# Pre_Charge_Interface.net
KiCad netlist of a schematic drawn in Altium Designer
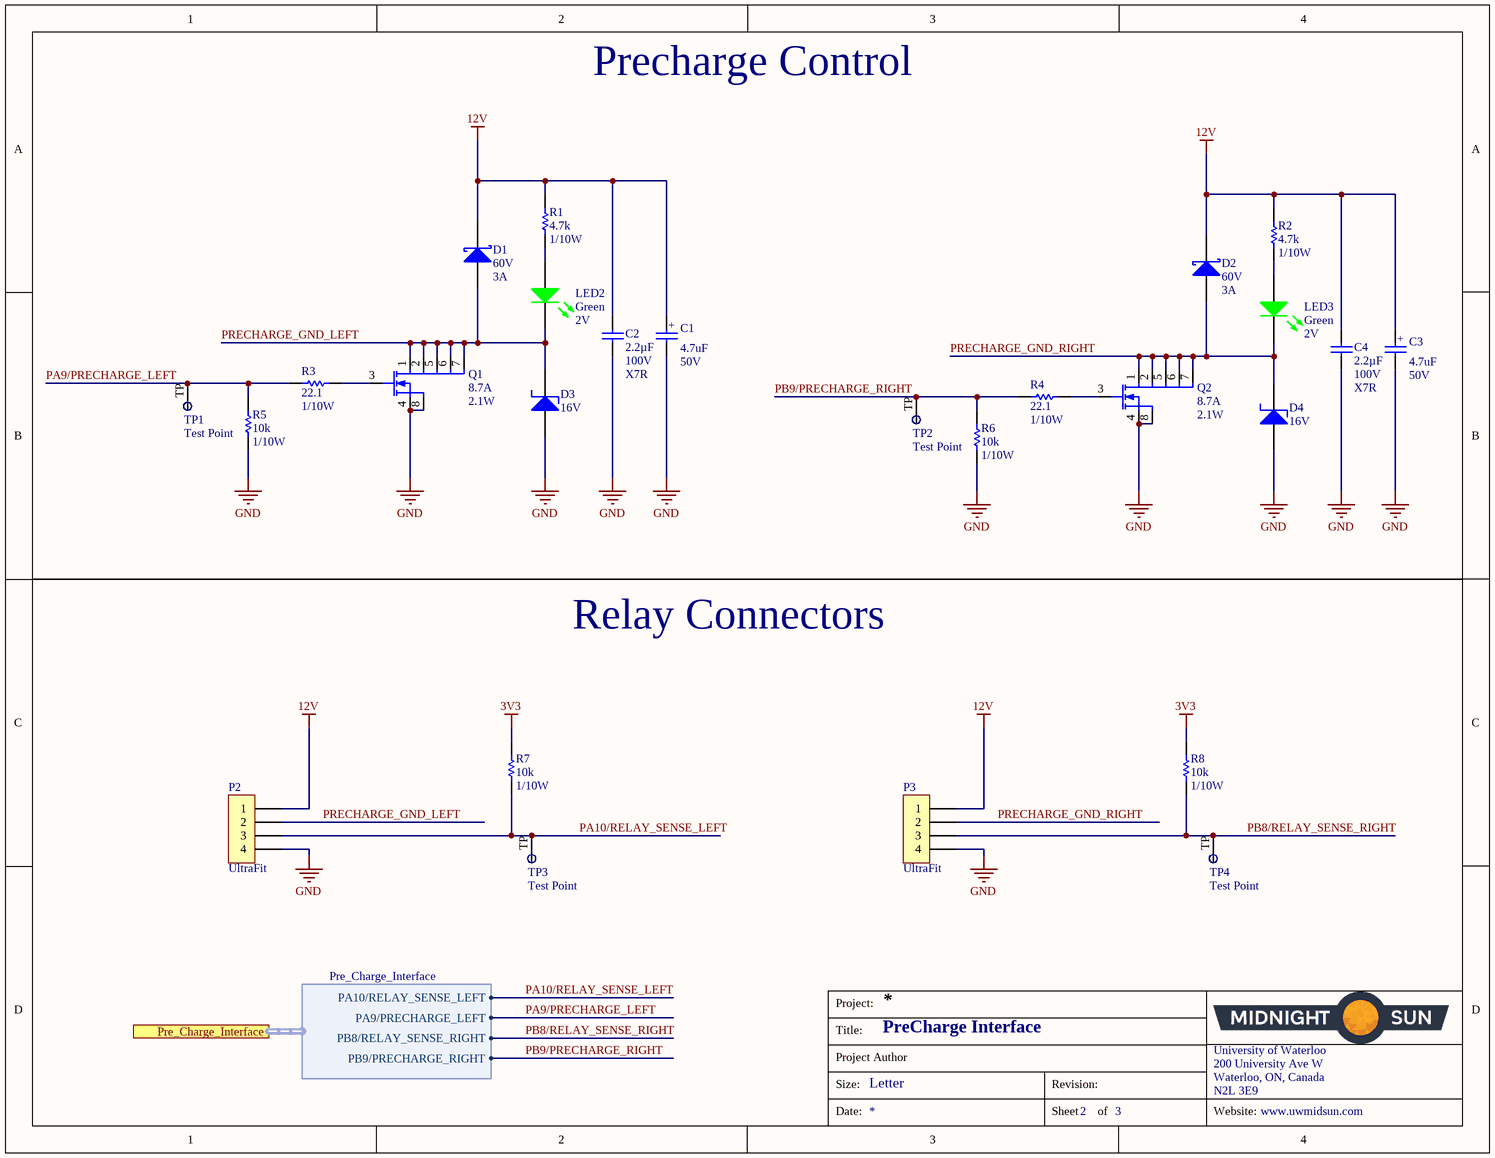
[diagram p0: Pre_Charge_Interface.SchDoc]

(export (version "E")
  (design (tool "Eeschema 10.0.6"))
  (components
    (comp (ref "C1")
      (value "EEE-1HA4R7NP")
      (footprint "CAP ALUM 6.3MM RADIAL SMD")
      (description "4.7µF 50V Aluminum Electrolytic Capacitors Radial, Can - SMD 2000 Hrs @ 85°C")
      (fields
        (field (name "TOLERANCE") "20%")
        (field (name "CAPACITANCE") "4.7uF")
        (field (name "VOLTAGE RATING (DC)") "50V")
      )
      (libsource (lib "Schematic Diagrams") (part "CAP ALUM 4.7UF 20% 50V SMD"))
    )
    (comp (ref "C2")
      (value "CAP CER 2.2UF 100V ±20% X7R 1206")
      (footprint "CAP, 1206")
      (description "2.2µF ±20% 100V Ceramic Capacitor X7R 1206 (3216 Metric)")
      (fields
        (field (name "TOLERANCE") "±20%")
        (field (name "CAPACITANCE") "2.2µF")
        (field (name "VOLTAGE") "100V")
        (field (name "TEMPERATURE COEFFICIENT") "X7R")
      )
      (libsource (lib "Schematic Diagrams") (part "CAP CER 2.2UF 100V ±20% X7R 1206"))
    )
    (comp (ref "C3")
      (value "EEE-1HA4R7NP")
      (footprint "CAP ALUM 6.3MM RADIAL SMD")
      (description "4.7µF 50V Aluminum Electrolytic Capacitors Radial, Can - SMD 2000 Hrs @ 85°C")
      (fields
        (field (name "TOLERANCE") "20%")
        (field (name "CAPACITANCE") "4.7uF")
        (field (name "VOLTAGE RATING (DC)") "50V")
      )
      (libsource (lib "Schematic Diagrams") (part "CAP ALUM 4.7UF 20% 50V SMD"))
    )
    (comp (ref "C4")
      (value "CAP CER 2.2UF 100V ±20% X7R 1206")
      (footprint "CAP, 1206")
      (description "2.2µF ±20% 100V Ceramic Capacitor X7R 1206 (3216 Metric)")
      (fields
        (field (name "TOLERANCE") "±20%")
        (field (name "CAPACITANCE") "2.2µF")
        (field (name "VOLTAGE") "100V")
        (field (name "TEMPERATURE COEFFICIENT") "X7R")
      )
      (libsource (lib "Schematic Diagrams") (part "CAP CER 2.2UF 100V ±20% X7R 1206"))
    )
    (comp (ref "D1")
      (value "DIODE SCHOTTKY 60V 3A SMA")
      (footprint "Diode, SMA")
      (description "Diode Schottky 60V 3A Surface Mount SMA")
      (fields
        (field (name "VOLTAGE - DC REVERSE (VR) (MAX)") "60V")
        (field (name "CURRENT - AVERAGE RECTIFIED (IO)") "3A")
      )
      (libsource (lib "Schematic Diagrams") (part "DIODE SCHOTTKY 60V 3A SMA"))
    )
    (comp (ref "D2")
      (value "DIODE SCHOTTKY 60V 3A SMA")
      (footprint "Diode, SMA")
      (description "Diode Schottky 60V 3A Surface Mount SMA")
      (fields
        (field (name "VOLTAGE - DC REVERSE (VR) (MAX)") "60V")
        (field (name "CURRENT - AVERAGE RECTIFIED (IO)") "3A")
      )
      (libsource (lib "Schematic Diagrams") (part "DIODE SCHOTTKY 60V 3A SMA"))
    )
    (comp (ref "D3")
      (value "DIODE ZENER 16V 5W DO-214AA (SMB)")
      (footprint "DO-214AA Diode")
      (description "Zener Diode 16V 5W ±5% Surface Mount DO-214AA (SMB)")
      (fields
        (field (name "MANUFACTURE PART NUMBER") "SMBJ5353B-TP")
        (field (name "VOLTAGE - ZENER (NOM)") "16V")
      )
      (libsource (lib "Schematic Diagrams") (part "DIODE ZENER 16V 5W DO-214AA (SMB)"))
    )
    (comp (ref "D4")
      (value "DIODE ZENER 16V 5W DO-214AA (SMB)")
      (footprint "DO-214AA Diode")
      (description "Zener Diode 16V 5W ±5% Surface Mount DO-214AA (SMB)")
      (fields
        (field (name "MANUFACTURE PART NUMBER") "SMBJ5353B-TP")
        (field (name "VOLTAGE - ZENER (NOM)") "16V")
      )
      (libsource (lib "Schematic Diagrams") (part "DIODE ZENER 16V 5W DO-214AA (SMB)"))
    )
    (comp (ref "LED2")
      (value "LED GREEN CLEAR 2V 0603")
      (footprint "LED_0603")
      (description "Green 572nm LED Indication - Discrete 2V 0603 (1608 Metric)")
      (fields
        (field (name "MANUFACTURER") "Wurth Electronics Inc.")
        (field (name "MANUFACTURER PART NUMBER") "150060VS75000")
        (field (name "COLOR") "Green")
        (field (name "VOLTAGE - FORWARD (VF) (TYP)") "2V")
      )
      (libsource (lib "Schematic Diagrams") (part "LED GREEN CLEAR 2V 0603"))
    )
    (comp (ref "LED3")
      (value "LED GREEN CLEAR 2V 0603")
      (footprint "LED_0603")
      (description "Green 572nm LED Indication - Discrete 2V 0603 (1608 Metric)")
      (fields
        (field (name "MANUFACTURER") "Wurth Electronics Inc.")
        (field (name "MANUFACTURER PART NUMBER") "150060VS75000")
        (field (name "COLOR") "Green")
        (field (name "VOLTAGE - FORWARD (VF) (TYP)") "2V")
      )
      (libsource (lib "Schematic Diagrams") (part "LED GREEN CLEAR 2V 0603"))
    )
    (comp (ref "P2")
      (value "CONN 4POS ULTRA-FIT 0.138\"")
      (footprint "CONN, 4POS ULTRA-FIT")
      (description "4 Positions Header Connector 0.138\" (3.50mm) Through Hole Tin")
      (fields (field (name "VOLTAGE") "400V") (field (name "SERIES") "UltraFit"))
      (libsource (lib "Schematic Diagrams") (part "CONN 4POS ULTRA-FIT 0.138{dblquote}"))
    )
    (comp (ref "P3")
      (value "CONN 4POS ULTRA-FIT 0.138\"")
      (footprint "CONN, 4POS ULTRA-FIT")
      (description "4 Positions Header Connector 0.138\" (3.50mm) Through Hole Tin")
      (fields (field (name "VOLTAGE") "400V") (field (name "SERIES") "UltraFit"))
      (libsource (lib "Schematic Diagrams") (part "CONN 4POS ULTRA-FIT 0.138{dblquote}"))
    )
    (comp (ref "Q1")
      (value "MOSFET N-CH 30V 8.7A 2.1W 6-PQFN (2x2)")
      (footprint "MOSFET N-CH 30V 12A 2mmx2mm PQFN")
      (fields
        (field (name "CURRENT - CONTINUOUS DRAIN (ID) @ 25°C") "8.7A")
        (field (name "POWER DISSIPATION (MAX)") "2.1W")
      )
      (libsource (lib "Schematic Diagrams") (part "MOSFET N-CH 30V 8.7A 2.1W 6-PQFN (2x2)"))
    )
    (comp (ref "Q2")
      (value "MOSFET N-CH 30V 8.7A 2.1W 6-PQFN (2x2)")
      (footprint "MOSFET N-CH 30V 12A 2mmx2mm PQFN")
      (fields
        (field (name "CURRENT - CONTINUOUS DRAIN (ID) @ 25°C") "8.7A")
        (field (name "POWER DISSIPATION (MAX)") "2.1W")
      )
      (libsource (lib "Schematic Diagrams") (part "MOSFET N-CH 30V 8.7A 2.1W 6-PQFN (2x2)"))
    )
    (comp (ref "R1")
      (value "RES 4.7K OHM 1% 1/10W 0603")
      (footprint "RES, 0603")
      (description "4.7k Ohm ±1% 0.1W, 1/10W Chip Resistor 0603 (1608 Metric) Moisture Resistant Thick Film")
      (fields
        (field (name "TOLERANCE") "±1%")
        (field (name "RESISTANCE (OHMS)") "4.7k")
        (field (name "POWER (WATTS)") "1/10W")
      )
      (libsource (lib "Schematic Diagrams") (part "RES 4.7K OHM 1% 1/10W 0603"))
    )
    (comp (ref "R2")
      (value "RES 4.7K OHM 1% 1/10W 0603")
      (footprint "RES, 0603")
      (description "4.7k Ohm ±1% 0.1W, 1/10W Chip Resistor 0603 (1608 Metric) Moisture Resistant Thick Film")
      (fields
        (field (name "TOLERANCE") "±1%")
        (field (name "RESISTANCE (OHMS)") "4.7k")
        (field (name "POWER (WATTS)") "1/10W")
      )
      (libsource (lib "Schematic Diagrams") (part "RES 4.7K OHM 1% 1/10W 0603"))
    )
    (comp (ref "R3")
      (value "RES 22.1 OHM 1% 1/10W 0603")
      (footprint "RES, 0603")
      (description "22.1 Ohm ±1% 0.1W, 1/10W Chip Resistor 0603 (1608 Metric) Moisture Resistant Thick Film")
      (fields
        (field (name "TOLERANCE") "±1%")
        (field (name "RESISTANCE") "22.1")
        (field (name "POWER") "1/10W")
      )
      (libsource (lib "Schematic Diagrams") (part "RES 22.1 OHM 1% 1/10W 0603"))
    )
    (comp (ref "R4")
      (value "RES 22.1 OHM 1% 1/10W 0603")
      (footprint "RES, 0603")
      (description "22.1 Ohm ±1% 0.1W, 1/10W Chip Resistor 0603 (1608 Metric) Moisture Resistant Thick Film")
      (fields
        (field (name "TOLERANCE") "±1%")
        (field (name "RESISTANCE") "22.1")
        (field (name "POWER") "1/10W")
      )
      (libsource (lib "Schematic Diagrams") (part "RES 22.1 OHM 1% 1/10W 0603"))
    )
    (comp (ref "R5")
      (value "RES 10K OHM 1% 1/10W 0603")
      (footprint "RES, 0603")
      (description "RES SMD 10K OHM 1% 1/10W 0603")
      (fields
        (field (name "TOLERANCE") "±1%")
        (field (name "RESISTANCE") "10k")
        (field (name "POWER") "1/10W")
      )
      (libsource (lib "Schematic Diagrams") (part "RES 10K OHM 1% 1/10W 0603"))
    )
    (comp (ref "R6")
      (value "RES 10K OHM 1% 1/10W 0603")
      (footprint "RES, 0603")
      (description "RES SMD 10K OHM 1% 1/10W 0603")
      (fields
        (field (name "TOLERANCE") "±1%")
        (field (name "RESISTANCE") "10k")
        (field (name "POWER") "1/10W")
      )
      (libsource (lib "Schematic Diagrams") (part "RES 10K OHM 1% 1/10W 0603"))
    )
    (comp (ref "R7")
      (value "RES 10K OHM 1% 1/10W 0603")
      (footprint "RES, 0603")
      (description "RES SMD 10K OHM 1% 1/10W 0603")
      (fields
        (field (name "TOLERANCE") "±1%")
        (field (name "RESISTANCE") "10k")
        (field (name "POWER") "1/10W")
      )
      (libsource (lib "Schematic Diagrams") (part "RES 10K OHM 1% 1/10W 0603"))
    )
    (comp (ref "R8")
      (value "RES 10K OHM 1% 1/10W 0603")
      (footprint "RES, 0603")
      (description "RES SMD 10K OHM 1% 1/10W 0603")
      (fields
        (field (name "TOLERANCE") "±1%")
        (field (name "RESISTANCE") "10k")
        (field (name "POWER") "1/10W")
      )
      (libsource (lib "Schematic Diagrams") (part "RES 10K OHM 1% 1/10W 0603"))
    )
    (comp (ref "TP1")
      (value "Test Point")
      (footprint "Test Point")
      (libsource (lib "Schematic Diagrams") (part "Test Point"))
    )
    (comp (ref "TP2")
      (value "Test Point")
      (footprint "Test Point")
      (libsource (lib "Schematic Diagrams") (part "Test Point"))
    )
    (comp (ref "TP3")
      (value "Test Point")
      (footprint "Test Point")
      (libsource (lib "Schematic Diagrams") (part "Test Point"))
    )
    (comp (ref "TP4")
      (value "Test Point")
      (footprint "Test Point")
      (libsource (lib "Schematic Diagrams") (part "Test Point"))
    )
  )
  (nets
    (net (code "2") (name "/PA9{slash}PRECHARGE_LEFT") (class "Default")
      (node (ref "R3") (pin "1") (pinfunction "1_1") (pintype "passive"))
      (node (ref "R5") (pin "1") (pinfunction "1_1") (pintype "passive"))
      (node (ref "TP1") (pin "TP") (pinfunction "1_TP") (pintype "passive"))
    )
    (net (code "3") (name "/PA10{slash}RELAY_SENSE_LEFT") (class "Default")
      (node (ref "P2") (pin "3") (pinfunction "3_3") (pintype "passive"))
      (node (ref "R7") (pin "2") (pinfunction "2_2") (pintype "passive"))
      (node (ref "TP3") (pin "TP") (pinfunction "1_TP") (pintype "passive"))
    )
    (net (code "4") (name "/PB8{slash}RELAY_SENSE_RIGHT") (class "Default")
      (node (ref "P3") (pin "3") (pinfunction "3_3") (pintype "passive"))
      (node (ref "R8") (pin "2") (pinfunction "2_2") (pintype "passive"))
      (node (ref "TP4") (pin "TP") (pinfunction "1_TP") (pintype "passive"))
    )
    (net (code "5") (name "/PB9{slash}PRECHARGE_RIGHT") (class "Default")
      (node (ref "R4") (pin "1") (pinfunction "1_1") (pintype "passive"))
      (node (ref "R6") (pin "1") (pinfunction "1_1") (pintype "passive"))
      (node (ref "TP2") (pin "TP") (pinfunction "1_TP") (pintype "passive"))
    )
    (net (code "6") (name "/PRECHARGE_GND_LEFT") (class "Default")
      (node (ref "D1") (pin "1") (pinfunction "1_1") (pintype "passive"))
      (node (ref "D3") (pin "2") (pinfunction "K_2") (pintype "passive"))
      (node (ref "LED2") (pin "2") (pinfunction "K_2") (pintype "passive"))
      (node (ref "P2") (pin "2") (pinfunction "2_2") (pintype "passive"))
      (node (ref "Q1") (pin "1") (pinfunction "D_1") (pintype "passive"))
      (node (ref "Q1") (pin "2") (pinfunction "D_2") (pintype "passive"))
      (node (ref "Q1") (pin "5") (pinfunction "D_5") (pintype "passive"))
      (node (ref "Q1") (pin "6") (pinfunction "D_6") (pintype "passive"))
      (node (ref "Q1") (pin "7") (pinfunction "D_7") (pintype "passive"))
    )
    (net (code "7") (name "/PRECHARGE_GND_RIGHT") (class "Default")
      (node (ref "D2") (pin "1") (pinfunction "1_1") (pintype "passive"))
      (node (ref "D4") (pin "2") (pinfunction "K_2") (pintype "passive"))
      (node (ref "LED3") (pin "2") (pinfunction "K_2") (pintype "passive"))
      (node (ref "P3") (pin "2") (pinfunction "2_2") (pintype "passive"))
      (node (ref "Q2") (pin "1") (pinfunction "D_1") (pintype "passive"))
      (node (ref "Q2") (pin "2") (pinfunction "D_2") (pintype "passive"))
      (node (ref "Q2") (pin "5") (pinfunction "D_5") (pintype "passive"))
      (node (ref "Q2") (pin "6") (pinfunction "D_6") (pintype "passive"))
      (node (ref "Q2") (pin "7") (pinfunction "D_7") (pintype "passive"))
    )
    (net (code "9") (name "3V3") (class "Default")
      (node (ref "R7") (pin "1") (pinfunction "1_1") (pintype "passive"))
      (node (ref "R8") (pin "1") (pinfunction "1_1") (pintype "passive"))
    )
    (net (code "10") (name "12V") (class "Default")
      (node (ref "C1") (pin "1") (pinfunction "1_1") (pintype "passive"))
      (node (ref "C2") (pin "1") (pinfunction "1_1") (pintype "passive"))
      (node (ref "C3") (pin "1") (pinfunction "1_1") (pintype "passive"))
      (node (ref "C4") (pin "1") (pinfunction "1_1") (pintype "passive"))
      (node (ref "D1") (pin "2") (pinfunction "2_2") (pintype "passive"))
      (node (ref "D2") (pin "2") (pinfunction "2_2") (pintype "passive"))
      (node (ref "P2") (pin "1") (pinfunction "1_1") (pintype "passive"))
      (node (ref "P3") (pin "1") (pinfunction "1_1") (pintype "passive"))
      (node (ref "R1") (pin "1") (pinfunction "1_1") (pintype "passive"))
      (node (ref "R2") (pin "1") (pinfunction "1_1") (pintype "passive"))
    )
    (net (code "11") (name "GND") (class "Default")
      (node (ref "C1") (pin "2") (pinfunction "2_2") (pintype "passive"))
      (node (ref "C2") (pin "2") (pinfunction "2_2") (pintype "passive"))
      (node (ref "C3") (pin "2") (pinfunction "2_2") (pintype "passive"))
      (node (ref "C4") (pin "2") (pinfunction "2_2") (pintype "passive"))
      (node (ref "D3") (pin "1") (pinfunction "A_1") (pintype "passive"))
      (node (ref "D4") (pin "1") (pinfunction "A_1") (pintype "passive"))
      (node (ref "P2") (pin "4") (pinfunction "4_4") (pintype "passive"))
      (node (ref "P3") (pin "4") (pinfunction "4_4") (pintype "passive"))
      (node (ref "Q1") (pin "4") (pinfunction "S_4") (pintype "passive"))
      (node (ref "Q1") (pin "8") (pinfunction "S_8") (pintype "passive"))
      (node (ref "Q2") (pin "4") (pinfunction "S_4") (pintype "passive"))
      (node (ref "Q2") (pin "8") (pinfunction "S_8") (pintype "passive"))
      (node (ref "R5") (pin "2") (pinfunction "2_2") (pintype "passive"))
      (node (ref "R6") (pin "2") (pinfunction "2_2") (pintype "passive"))
    )
    (net (code "12") (name "Net-(LED2-A)") (class "Default")
      (node (ref "LED2") (pin "1") (pinfunction "A_1") (pintype "passive"))
      (node (ref "R1") (pin "2") (pinfunction "2_2") (pintype "passive"))
    )
    (net (code "13") (name "Net-(LED3-A)") (class "Default")
      (node (ref "LED3") (pin "1") (pinfunction "A_1") (pintype "passive"))
      (node (ref "R2") (pin "2") (pinfunction "2_2") (pintype "passive"))
    )
    (net (code "14") (name "Net-(Q1-G)") (class "Default")
      (node (ref "Q1") (pin "3") (pinfunction "G_3") (pintype "passive"))
      (node (ref "R3") (pin "2") (pinfunction "2_2") (pintype "passive"))
    )
    (net (code "15") (name "Net-(Q2-G)") (class "Default")
      (node (ref "Q2") (pin "3") (pinfunction "G_3") (pintype "passive"))
      (node (ref "R4") (pin "2") (pinfunction "2_2") (pintype "passive"))
    )
  )
)
